# RobotCtrl_Power.net
KiCad netlist of a schematic drawn in Altium Designer
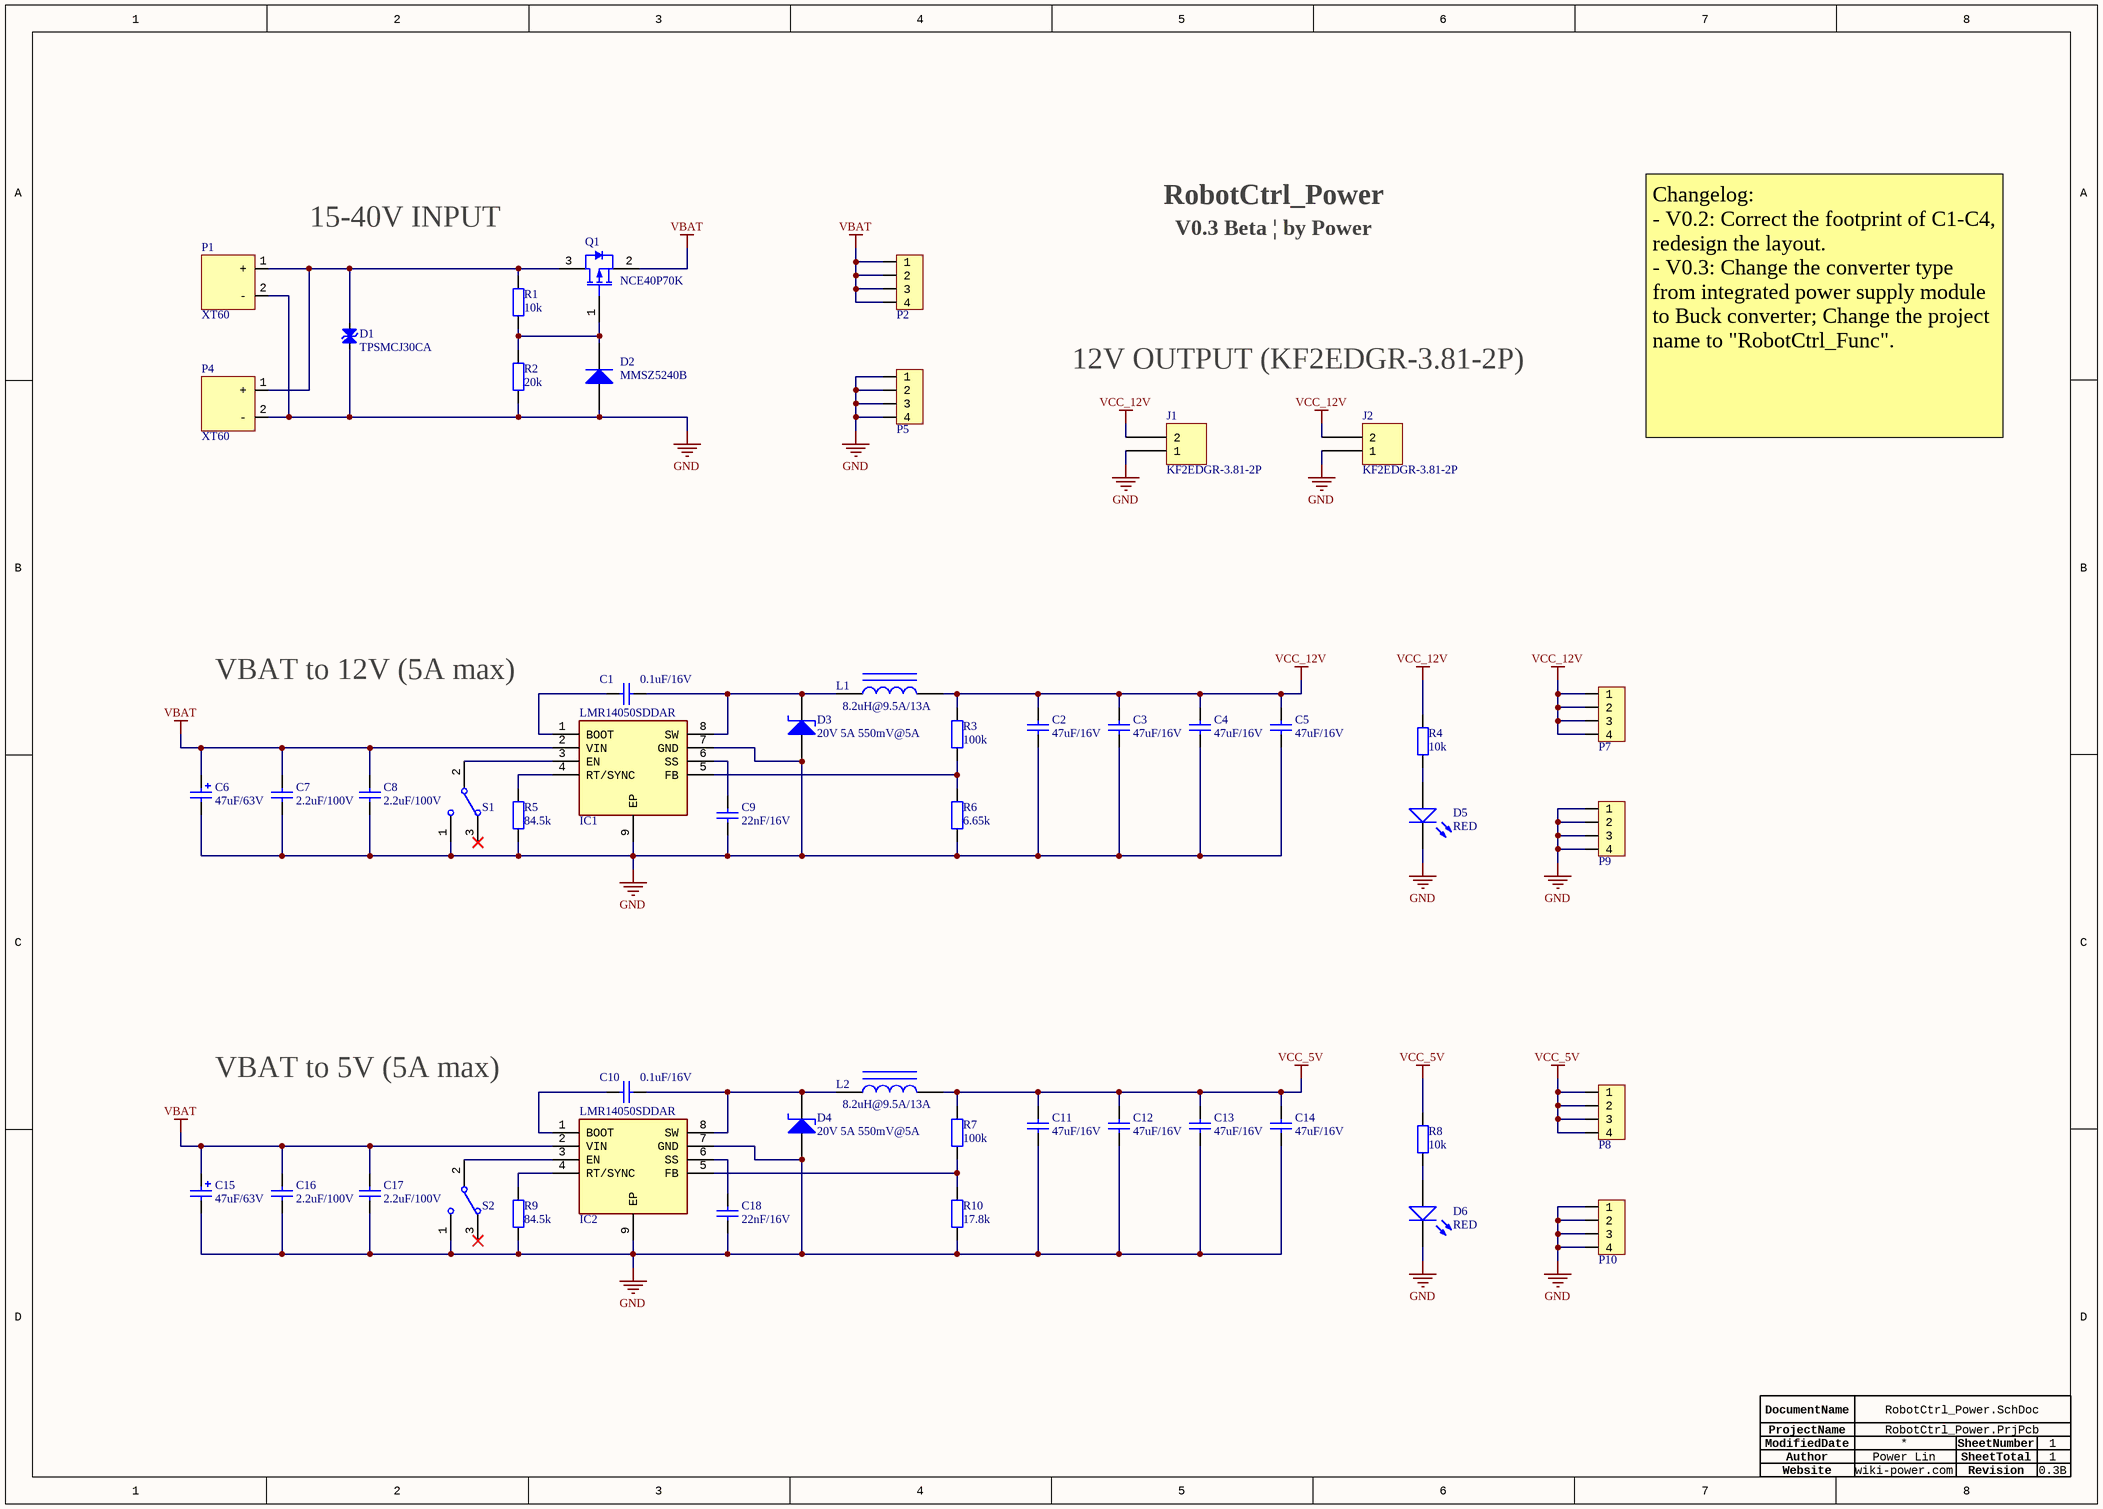
[diagram p0: RobotCtrl_Power.SchDoc]

(export (version "E")
  (design (tool "Eeschema 10.0.6"))
  (components
    (comp (ref "C1")
      (value "0.1uF/16V")
      (footprint "CAP-0603")
      (description "CC0603KRX7R7BB104")
      (libsource (lib "Power_Lib_Altium") (part "CAP"))
    )
    (comp (ref "C2")
      (value "47uF/16V")
      (footprint "CAP-1210")
      (description "C1210X5R476K160NT")
      (libsource (lib "Power_Lib_Altium") (part "CAP"))
    )
    (comp (ref "C3")
      (value "47uF/16V")
      (footprint "CAP-1210")
      (description "C1210X5R476K160NT")
      (libsource (lib "Power_Lib_Altium") (part "CAP"))
    )
    (comp (ref "C4")
      (value "47uF/16V")
      (footprint "CAP-1210")
      (description "C1210X5R476K160NT")
      (libsource (lib "Power_Lib_Altium") (part "CAP"))
    )
    (comp (ref "C5")
      (value "47uF/16V")
      (footprint "CAP-1210")
      (description "C1210X5R476K160NT")
      (libsource (lib "Power_Lib_Altium") (part "CAP"))
    )
    (comp (ref "C6")
      (value "47uF/63V")
      (footprint "C_SMD-8X10")
      (description "RVT1J470M0810")
      (libsource (lib "Power_Lib_Altium") (part "CAP-POL"))
    )
    (comp (ref "C7")
      (value "2.2uF/100V")
      (footprint "CAP-1206")
      (description "CS3216X7R225K101NRI")
      (libsource (lib "Power_Lib_Altium") (part "CAP"))
    )
    (comp (ref "C8")
      (value "2.2uF/100V")
      (footprint "CAP-1206")
      (description "CS3216X7R225K101NRI")
      (libsource (lib "Power_Lib_Altium") (part "CAP"))
    )
    (comp (ref "C9")
      (value "22nF/16V")
      (footprint "CAP-0603")
      (description "CC0603KRX7R7BB223")
      (libsource (lib "Power_Lib_Altium") (part "CAP"))
    )
    (comp (ref "C10")
      (value "0.1uF/16V")
      (footprint "CAP-0603")
      (description "CC0603KRX7R7BB104")
      (libsource (lib "Power_Lib_Altium") (part "CAP"))
    )
    (comp (ref "C11")
      (value "47uF/16V")
      (footprint "CAP-1210")
      (description "C1210X5R476K160NT")
      (libsource (lib "Power_Lib_Altium") (part "CAP"))
    )
    (comp (ref "C12")
      (value "47uF/16V")
      (footprint "CAP-1210")
      (description "C1210X5R476K160NT")
      (libsource (lib "Power_Lib_Altium") (part "CAP"))
    )
    (comp (ref "C13")
      (value "47uF/16V")
      (footprint "CAP-1210")
      (description "C1210X5R476K160NT")
      (libsource (lib "Power_Lib_Altium") (part "CAP"))
    )
    (comp (ref "C14")
      (value "47uF/16V")
      (footprint "CAP-1210")
      (description "C1210X5R476K160NT")
      (libsource (lib "Power_Lib_Altium") (part "CAP"))
    )
    (comp (ref "C15")
      (value "47uF/63V")
      (footprint "C_SMD-8X10")
      (description "RVT1J470M0810")
      (libsource (lib "Power_Lib_Altium") (part "CAP-POL"))
    )
    (comp (ref "C16")
      (value "2.2uF/100V")
      (footprint "CAP-1206")
      (description "CS3216X7R225K101NRI")
      (libsource (lib "Power_Lib_Altium") (part "CAP"))
    )
    (comp (ref "C17")
      (value "2.2uF/100V")
      (footprint "CAP-1206")
      (description "CS3216X7R225K101NRI")
      (libsource (lib "Power_Lib_Altium") (part "CAP"))
    )
    (comp (ref "C18")
      (value "22nF/16V")
      (footprint "CAP-0603")
      (description "CC0603KRX7R7BB223")
      (libsource (lib "Power_Lib_Altium") (part "CAP"))
    )
    (comp (ref "D1")
      (value "TPSMCJ30CA")
      (footprint "DO-214AB/SMC")
      (libsource (lib "Power_Lib_Altium") (part "TVS_C"))
    )
    (comp (ref "D2")
      (value "MMSZ5240B")
      (footprint "SOD_123")
      (description "稳压 10V")
      (libsource (lib "Power_Lib_Altium") (part "DIODE"))
    )
    (comp (ref "D3")
      (value "20V 5A 550mV@5A")
      (footprint "DO-214AB/SMC")
      (description "SS52")
      (libsource (lib "Power_Lib_Altium") (part "DIODE_Schottky"))
    )
    (comp (ref "D4")
      (value "20V 5A 550mV@5A")
      (footprint "DO-214AB/SMC")
      (description "SS52")
      (libsource (lib "Power_Lib_Altium") (part "DIODE_Schottky"))
    )
    (comp (ref "D5")
      (value "RED")
      (footprint "LED-0603")
      (description "发光二极管")
      (libsource (lib "Power_Lib_Altium") (part "LED"))
    )
    (comp (ref "D6")
      (value "RED")
      (footprint "LED-0603")
      (description "发光二极管")
      (libsource (lib "Power_Lib_Altium") (part "LED"))
    )
    (comp (ref "IC1")
      (value "LMR14050SDDAR")
      (footprint "HSOIC-8")
      (fields (field (name "MOUSER PART NUMBER") "595-LMR14050SDDAR"))
      (libsource (lib "Power_Lib_Altium") (part "LMR14050SDDAR"))
    )
    (comp (ref "IC2")
      (value "LMR14050SDDAR")
      (footprint "HSOIC-8")
      (fields (field (name "MOUSER PART NUMBER") "595-LMR14050SDDAR"))
      (libsource (lib "Power_Lib_Altium") (part "LMR14050SDDAR"))
    )
    (comp (ref "J1")
      (value "KF2EDGR-3.81-2P")
      (footprint "FCI 06-381-2PIN")
      (description "TERM BLOCK HDR 2POS 90DEG 3.81MM")
      (fields (field (name "PART NUMBER") "OQ0232510000G") (field (name "MANUFACTURER") "Amphenol Anytek"))
      (libsource (lib "Power_Lib_Altium") (part "KF2EDGR-3.81-2P"))
    )
    (comp (ref "J2")
      (value "KF2EDGR-3.81-2P")
      (footprint "FCI 06-381-2PIN")
      (description "TERM BLOCK HDR 2POS 90DEG 3.81MM")
      (fields (field (name "PART NUMBER") "OQ0232510000G") (field (name "MANUFACTURER") "Amphenol Anytek"))
      (libsource (lib "Power_Lib_Altium") (part "KF2EDGR-3.81-2P"))
    )
    (comp (ref "L1")
      (value "8.2uH@9.5A/13A")
      (footprint "SMD-13.45x12.6x4.8mm")
      (description "MDE1250-8R2M")
      (libsource (lib "Power_Lib_Altium") (part "INDUCTOR"))
    )
    (comp (ref "L2")
      (value "8.2uH@9.5A/13A")
      (footprint "SMD-13.45x12.6x4.8mm")
      (description "MDE1250-8R2M")
      (libsource (lib "Power_Lib_Altium") (part "INDUCTOR"))
    )
    (comp (ref "P1")
      (value "XT60")
      (footprint "XT60PW-M")
      (libsource (lib "Power_Lib_Altium") (part "XT30/60"))
    )
    (comp (ref "P2")
      (value "HDR1x4_2.54")
      (footprint "HDR1x4_2.54_180")
      (description "Header")
      (libsource (lib "Power_Lib_Altium") (part "HDR1x4_2.54"))
    )
    (comp (ref "P4")
      (value "XT60")
      (footprint "XT60PW-M")
      (libsource (lib "Power_Lib_Altium") (part "XT30/60"))
    )
    (comp (ref "P5")
      (value "HDR1x4_2.54")
      (footprint "HDR1x4_2.54_180")
      (description "Header")
      (libsource (lib "Power_Lib_Altium") (part "HDR1x4_2.54"))
    )
    (comp (ref "P7")
      (value "HDR1x4_2.54")
      (footprint "HDR1x4_2.54_180")
      (description "Header")
      (libsource (lib "Power_Lib_Altium") (part "HDR1x4_2.54"))
    )
    (comp (ref "P8")
      (value "HDR1x4_2.54")
      (footprint "HDR1x4_2.54_180")
      (description "Header")
      (libsource (lib "Power_Lib_Altium") (part "HDR1x4_2.54"))
    )
    (comp (ref "P9")
      (value "HDR1x4_2.54")
      (footprint "HDR1x4_2.54_180")
      (description "Header")
      (libsource (lib "Power_Lib_Altium") (part "HDR1x4_2.54"))
    )
    (comp (ref "P10")
      (value "HDR1x4_2.54")
      (footprint "HDR1x4_2.54_180")
      (description "Header")
      (libsource (lib "Power_Lib_Altium") (part "HDR1x4_2.54"))
    )
    (comp (ref "Q1")
      (value "NCE40P70K")
      (footprint "TO-252")
      (fields (field (name "MANUFACTURER") "NCE Power"))
      (libsource (lib "Power_Lib_Altium") (part "P-MOS"))
    )
    (comp (ref "R1")
      (value "10k")
      (footprint "R-0603")
      (description "贴片电阻")
      (libsource (lib "") (part "RES_1"))
    )
    (comp (ref "R2")
      (value "20k")
      (footprint "R-0603")
      (description "贴片电阻")
      (libsource (lib "") (part "RES_1"))
    )
    (comp (ref "R3")
      (value "100k")
      (footprint "R-0603")
      (description "RC0603FR-07100KL")
      (libsource (lib "Power_Lib_Altium") (part "RES"))
    )
    (comp (ref "R4")
      (value "10k")
      (footprint "R-0603")
      (description "贴片电阻")
      (libsource (lib "") (part "RES_1"))
    )
    (comp (ref "R5")
      (value "84.5k")
      (footprint "R-0603")
      (description "RC0603FR-0784K5L")
      (libsource (lib "Power_Lib_Altium") (part "RES"))
    )
    (comp (ref "R6")
      (value "6.65k")
      (footprint "R-0603")
      (description "RC0603FR-076K65L")
      (libsource (lib "Power_Lib_Altium") (part "RES"))
    )
    (comp (ref "R7")
      (value "100k")
      (footprint "R-0603")
      (description "RC0603FR-07100KL")
      (libsource (lib "Power_Lib_Altium") (part "RES"))
    )
    (comp (ref "R8")
      (value "10k")
      (footprint "R-0603")
      (description "贴片电阻")
      (libsource (lib "") (part "RES_1"))
    )
    (comp (ref "R9")
      (value "84.5k")
      (footprint "R-0603")
      (description "RC0603FR-0784K5L")
      (libsource (lib "Power_Lib_Altium") (part "RES"))
    )
    (comp (ref "R10")
      (value "17.8k")
      (footprint "R-0603")
      (description "RC0603FR-0717K8L")
      (libsource (lib "Power_Lib_Altium") (part "RES"))
    )
    (comp (ref "S1")
      (value "Switch_SPDT")
      (footprint "SwitchSPDT_2.8X6.6_90")
      (description "TA-3524A-A1")
      (libsource (lib "Power_Lib_Altium") (part "Switch_SPDT"))
    )
    (comp (ref "S2")
      (value "Switch_SPDT")
      (footprint "SwitchSPDT_2.8X6.6_90")
      (description "TA-3524A-A1")
      (libsource (lib "Power_Lib_Altium") (part "Switch_SPDT"))
    )
  )
  (nets
    (net (code "1") (name "GND") (class "Default")
      (node (ref "C11") (pin "1") (pinfunction "1_1") (pintype "passive"))
      (node (ref "C12") (pin "1") (pinfunction "1_1") (pintype "passive"))
      (node (ref "C13") (pin "1") (pinfunction "1_1") (pintype "passive"))
      (node (ref "C14") (pin "1") (pinfunction "1_1") (pintype "passive"))
      (node (ref "C15") (pin "2") (pinfunction "2_2") (pintype "passive"))
      (node (ref "C16") (pin "1") (pinfunction "1_1") (pintype "passive"))
      (node (ref "C17") (pin "1") (pinfunction "1_1") (pintype "passive"))
      (node (ref "C18") (pin "1") (pinfunction "1_1") (pintype "passive"))
      (node (ref "C2") (pin "1") (pinfunction "1_1") (pintype "passive"))
      (node (ref "C3") (pin "1") (pinfunction "1_1") (pintype "passive"))
      (node (ref "C4") (pin "1") (pinfunction "1_1") (pintype "passive"))
      (node (ref "C5") (pin "1") (pinfunction "1_1") (pintype "passive"))
      (node (ref "C6") (pin "2") (pinfunction "2_2") (pintype "passive"))
      (node (ref "C7") (pin "1") (pinfunction "1_1") (pintype "passive"))
      (node (ref "C8") (pin "1") (pinfunction "1_1") (pintype "passive"))
      (node (ref "C9") (pin "1") (pinfunction "1_1") (pintype "passive"))
      (node (ref "D1") (pin "1") (pinfunction "1_1") (pintype "passive"))
      (node (ref "D2") (pin "1") (pinfunction "A_1") (pintype "passive"))
      (node (ref "D3") (pin "1") (pinfunction "A_1") (pintype "passive"))
      (node (ref "D4") (pin "1") (pinfunction "A_1") (pintype "passive"))
      (node (ref "D5") (pin "K") (pinfunction "K_K") (pintype "passive"))
      (node (ref "D6") (pin "K") (pinfunction "K_K") (pintype "passive"))
      (node (ref "IC1") (pin "7") (pinfunction "GND_7") (pintype "passive"))
      (node (ref "IC1") (pin "9") (pinfunction "EP_9") (pintype "passive"))
      (node (ref "IC2") (pin "7") (pinfunction "GND_7") (pintype "passive"))
      (node (ref "IC2") (pin "9") (pinfunction "EP_9") (pintype "passive"))
      (node (ref "J1") (pin "1") (pinfunction "1_1") (pintype "passive"))
      (node (ref "J2") (pin "1") (pinfunction "1_1") (pintype "passive"))
      (node (ref "P1") (pin "2") (pinfunction "-_2") (pintype "passive"))
      (node (ref "P10") (pin "1") (pinfunction "1_1") (pintype "passive"))
      (node (ref "P10") (pin "2") (pinfunction "2_2") (pintype "passive"))
      (node (ref "P10") (pin "3") (pinfunction "3_3") (pintype "passive"))
      (node (ref "P10") (pin "4") (pinfunction "4_4") (pintype "passive"))
      (node (ref "P4") (pin "2") (pinfunction "-_2") (pintype "passive"))
      (node (ref "P5") (pin "1") (pinfunction "1_1") (pintype "passive"))
      (node (ref "P5") (pin "2") (pinfunction "2_2") (pintype "passive"))
      (node (ref "P5") (pin "3") (pinfunction "3_3") (pintype "passive"))
      (node (ref "P5") (pin "4") (pinfunction "4_4") (pintype "passive"))
      (node (ref "P9") (pin "1") (pinfunction "1_1") (pintype "passive"))
      (node (ref "P9") (pin "2") (pinfunction "2_2") (pintype "passive"))
      (node (ref "P9") (pin "3") (pinfunction "3_3") (pintype "passive"))
      (node (ref "P9") (pin "4") (pinfunction "4_4") (pintype "passive"))
      (node (ref "R10") (pin "1") (pinfunction "1_1") (pintype "passive"))
      (node (ref "R2") (pin "2") (pinfunction "2_2") (pintype "passive"))
      (node (ref "R5") (pin "1") (pinfunction "1_1") (pintype "passive"))
      (node (ref "R6") (pin "1") (pinfunction "1_1") (pintype "passive"))
      (node (ref "R9") (pin "1") (pinfunction "1_1") (pintype "passive"))
      (node (ref "S1") (pin "1") (pinfunction "1_1") (pintype "passive"))
      (node (ref "S2") (pin "1") (pinfunction "1_1") (pintype "passive"))
    )
    (net (code "2") (name "Net-(D2-K)") (class "Default")
      (node (ref "D2") (pin "2") (pinfunction "K_2") (pintype "passive"))
      (node (ref "Q1") (pin "1") (pinfunction "GATE_1") (pintype "passive"))
      (node (ref "R1") (pin "2") (pinfunction "2_2") (pintype "passive"))
      (node (ref "R2") (pin "1") (pinfunction "1_1") (pintype "passive"))
    )
    (net (code "3") (name "Net-(D3-K)") (class "Default")
      (node (ref "C1") (pin "2") (pinfunction "2_2") (pintype "passive"))
      (node (ref "D3") (pin "2") (pinfunction "K_2") (pintype "passive"))
      (node (ref "IC1") (pin "8") (pinfunction "SW_8") (pintype "passive"))
      (node (ref "L1") (pin "1") (pinfunction "1_1") (pintype "passive"))
    )
    (net (code "4") (name "Net-(D4-K)") (class "Default")
      (node (ref "C10") (pin "2") (pinfunction "2_2") (pintype "passive"))
      (node (ref "D4") (pin "2") (pinfunction "K_2") (pintype "passive"))
      (node (ref "IC2") (pin "8") (pinfunction "SW_8") (pintype "passive"))
      (node (ref "L2") (pin "1") (pinfunction "1_1") (pintype "passive"))
    )
    (net (code "5") (name "Net-(D5-PadA)") (class "Default")
      (node (ref "D5") (pin "A") (pinfunction "A_A") (pintype "passive"))
      (node (ref "R4") (pin "2") (pinfunction "2_2") (pintype "passive"))
    )
    (net (code "6") (name "Net-(D6-PadA)") (class "Default")
      (node (ref "D6") (pin "A") (pinfunction "A_A") (pintype "passive"))
      (node (ref "R8") (pin "2") (pinfunction "2_2") (pintype "passive"))
    )
    (net (code "7") (name "Net-(IC1-BOOT)") (class "Default")
      (node (ref "C1") (pin "1") (pinfunction "1_1") (pintype "passive"))
      (node (ref "IC1") (pin "1") (pinfunction "BOOT_1") (pintype "passive"))
    )
    (net (code "8") (name "Net-(IC1-EN)") (class "Default")
      (node (ref "IC1") (pin "3") (pinfunction "EN_3") (pintype "passive"))
      (node (ref "S1") (pin "2") (pinfunction "2_2") (pintype "passive"))
    )
    (net (code "9") (name "Net-(IC1-FB)") (class "Default")
      (node (ref "IC1") (pin "5") (pinfunction "FB_5") (pintype "passive"))
      (node (ref "R3") (pin "1") (pinfunction "1_1") (pintype "passive"))
      (node (ref "R6") (pin "2") (pinfunction "2_2") (pintype "passive"))
    )
    (net (code "10") (name "Net-(IC1-RT{slash}SYNC)") (class "Default")
      (node (ref "IC1") (pin "4") (pinfunction "RT/SYNC_4") (pintype "passive"))
      (node (ref "R5") (pin "2") (pinfunction "2_2") (pintype "passive"))
    )
    (net (code "11") (name "Net-(IC1-SS)") (class "Default")
      (node (ref "C9") (pin "2") (pinfunction "2_2") (pintype "passive"))
      (node (ref "IC1") (pin "6") (pinfunction "SS_6") (pintype "passive"))
    )
    (net (code "12") (name "Net-(IC2-BOOT)") (class "Default")
      (node (ref "C10") (pin "1") (pinfunction "1_1") (pintype "passive"))
      (node (ref "IC2") (pin "1") (pinfunction "BOOT_1") (pintype "passive"))
    )
    (net (code "13") (name "Net-(IC2-EN)") (class "Default")
      (node (ref "IC2") (pin "3") (pinfunction "EN_3") (pintype "passive"))
      (node (ref "S2") (pin "2") (pinfunction "2_2") (pintype "passive"))
    )
    (net (code "14") (name "Net-(IC2-FB)") (class "Default")
      (node (ref "IC2") (pin "5") (pinfunction "FB_5") (pintype "passive"))
      (node (ref "R10") (pin "2") (pinfunction "2_2") (pintype "passive"))
      (node (ref "R7") (pin "1") (pinfunction "1_1") (pintype "passive"))
    )
    (net (code "15") (name "Net-(IC2-RT{slash}SYNC)") (class "Default")
      (node (ref "IC2") (pin "4") (pinfunction "RT/SYNC_4") (pintype "passive"))
      (node (ref "R9") (pin "2") (pinfunction "2_2") (pintype "passive"))
    )
    (net (code "16") (name "Net-(IC2-SS)") (class "Default")
      (node (ref "C18") (pin "2") (pinfunction "2_2") (pintype "passive"))
      (node (ref "IC2") (pin "6") (pinfunction "SS_6") (pintype "passive"))
    )
    (net (code "17") (name "Net-(P1-+)") (class "Default")
      (node (ref "D1") (pin "2") (pinfunction "2_2") (pintype "passive"))
      (node (ref "P1") (pin "1") (pinfunction "+_1") (pintype "passive"))
      (node (ref "P4") (pin "1") (pinfunction "+_1") (pintype "passive"))
      (node (ref "Q1") (pin "3") (pinfunction "DRAIN_3") (pintype "passive"))
      (node (ref "R1") (pin "1") (pinfunction "1_1") (pintype "passive"))
    )
    (net (code "18") (name "VBAT") (class "Default")
      (node (ref "C15") (pin "1") (pinfunction "1_1") (pintype "passive"))
      (node (ref "C16") (pin "2") (pinfunction "2_2") (pintype "passive"))
      (node (ref "C17") (pin "2") (pinfunction "2_2") (pintype "passive"))
      (node (ref "C6") (pin "1") (pinfunction "1_1") (pintype "passive"))
      (node (ref "C7") (pin "2") (pinfunction "2_2") (pintype "passive"))
      (node (ref "C8") (pin "2") (pinfunction "2_2") (pintype "passive"))
      (node (ref "IC1") (pin "2") (pinfunction "VIN_2") (pintype "passive"))
      (node (ref "IC2") (pin "2") (pinfunction "VIN_2") (pintype "passive"))
      (node (ref "P2") (pin "1") (pinfunction "1_1") (pintype "passive"))
      (node (ref "P2") (pin "2") (pinfunction "2_2") (pintype "passive"))
      (node (ref "P2") (pin "3") (pinfunction "3_3") (pintype "passive"))
      (node (ref "P2") (pin "4") (pinfunction "4_4") (pintype "passive"))
      (node (ref "Q1") (pin "2") (pinfunction "SOURCE_2") (pintype "passive"))
    )
    (net (code "19") (name "VCC_5V") (class "Default")
      (node (ref "C11") (pin "2") (pinfunction "2_2") (pintype "passive"))
      (node (ref "C12") (pin "2") (pinfunction "2_2") (pintype "passive"))
      (node (ref "C13") (pin "2") (pinfunction "2_2") (pintype "passive"))
      (node (ref "C14") (pin "2") (pinfunction "2_2") (pintype "passive"))
      (node (ref "L2") (pin "2") (pinfunction "2_2") (pintype "passive"))
      (node (ref "P8") (pin "1") (pinfunction "1_1") (pintype "passive"))
      (node (ref "P8") (pin "2") (pinfunction "2_2") (pintype "passive"))
      (node (ref "P8") (pin "3") (pinfunction "3_3") (pintype "passive"))
      (node (ref "P8") (pin "4") (pinfunction "4_4") (pintype "passive"))
      (node (ref "R7") (pin "2") (pinfunction "2_2") (pintype "passive"))
      (node (ref "R8") (pin "1") (pinfunction "1_1") (pintype "passive"))
    )
    (net (code "20") (name "VCC_12V") (class "Default")
      (node (ref "C2") (pin "2") (pinfunction "2_2") (pintype "passive"))
      (node (ref "C3") (pin "2") (pinfunction "2_2") (pintype "passive"))
      (node (ref "C4") (pin "2") (pinfunction "2_2") (pintype "passive"))
      (node (ref "C5") (pin "2") (pinfunction "2_2") (pintype "passive"))
      (node (ref "J1") (pin "2") (pinfunction "2_2") (pintype "passive"))
      (node (ref "J2") (pin "2") (pinfunction "2_2") (pintype "passive"))
      (node (ref "L1") (pin "2") (pinfunction "2_2") (pintype "passive"))
      (node (ref "P7") (pin "1") (pinfunction "1_1") (pintype "passive"))
      (node (ref "P7") (pin "2") (pinfunction "2_2") (pintype "passive"))
      (node (ref "P7") (pin "3") (pinfunction "3_3") (pintype "passive"))
      (node (ref "P7") (pin "4") (pinfunction "4_4") (pintype "passive"))
      (node (ref "R3") (pin "2") (pinfunction "2_2") (pintype "passive"))
      (node (ref "R4") (pin "1") (pinfunction "1_1") (pintype "passive"))
    )
    (net (code "21") (name "unconnected-(S1-Pad3)") (class "Default")
      (node (ref "S1") (pin "3") (pinfunction "3_3") (pintype "passive+no_connect"))
    )
    (net (code "22") (name "unconnected-(S2-Pad3)") (class "Default")
      (node (ref "S2") (pin "3") (pinfunction "3_3") (pintype "passive+no_connect"))
    )
  )
)
